# untitled.net
KiCad netlist of a schematic drawn in EAGLE
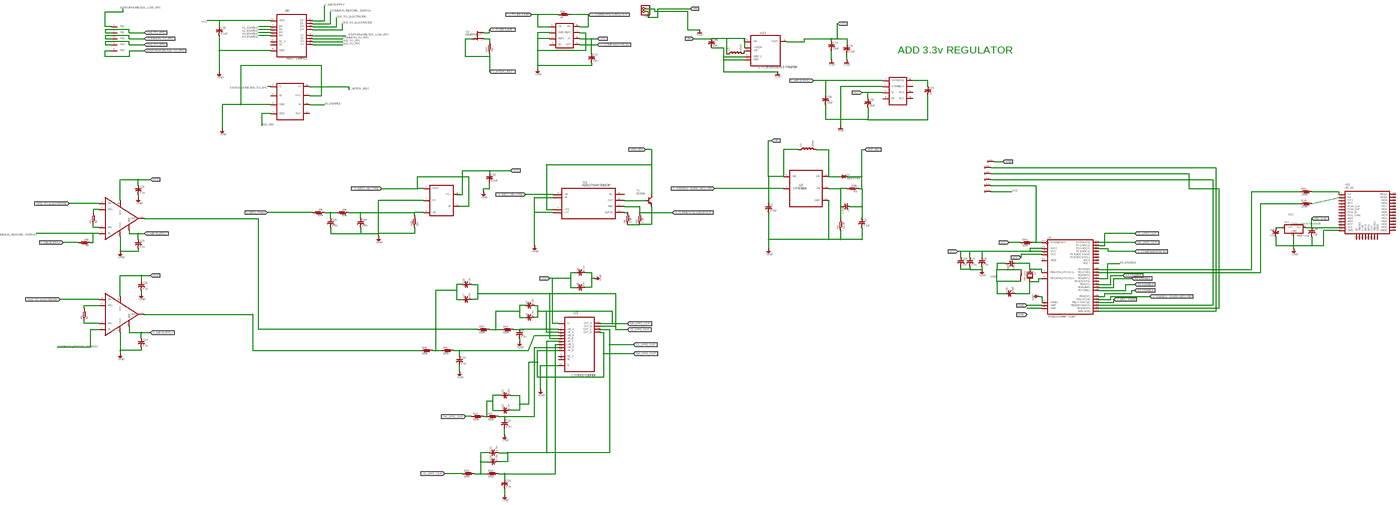
[diagram p0: schematic, sheet 1, overview]
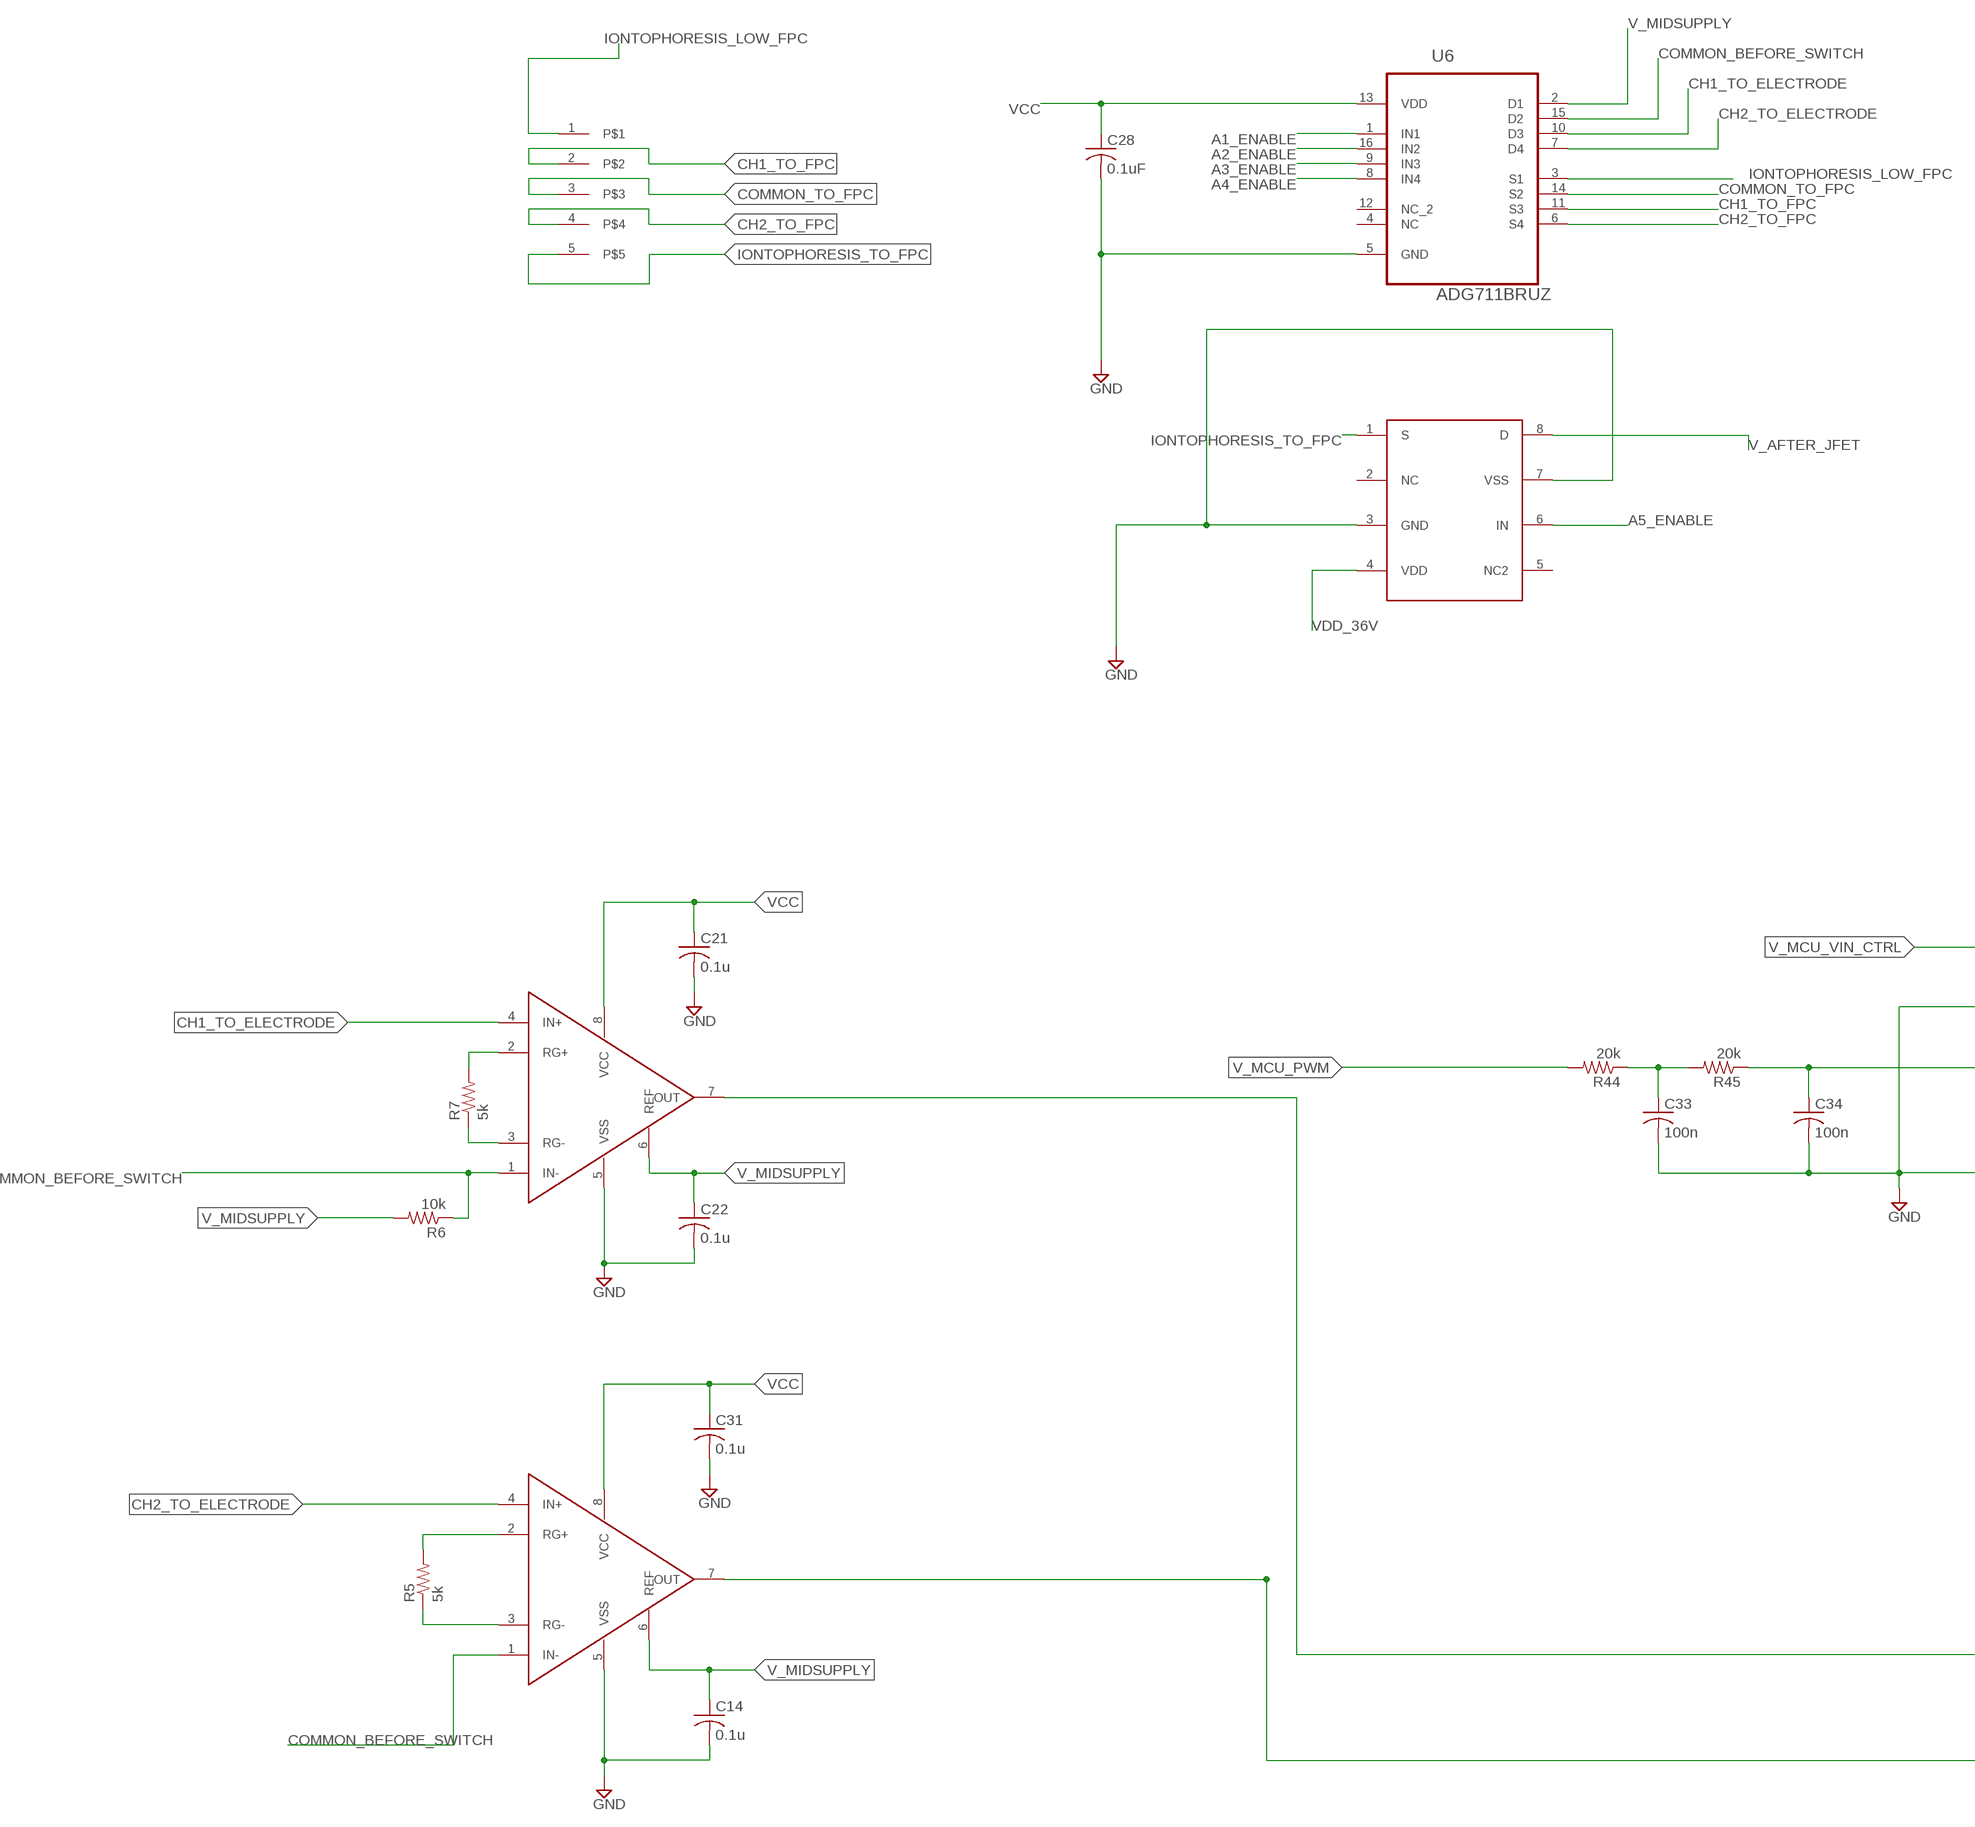
[diagram p1: schematic, sheet 1, part 1 of 4]
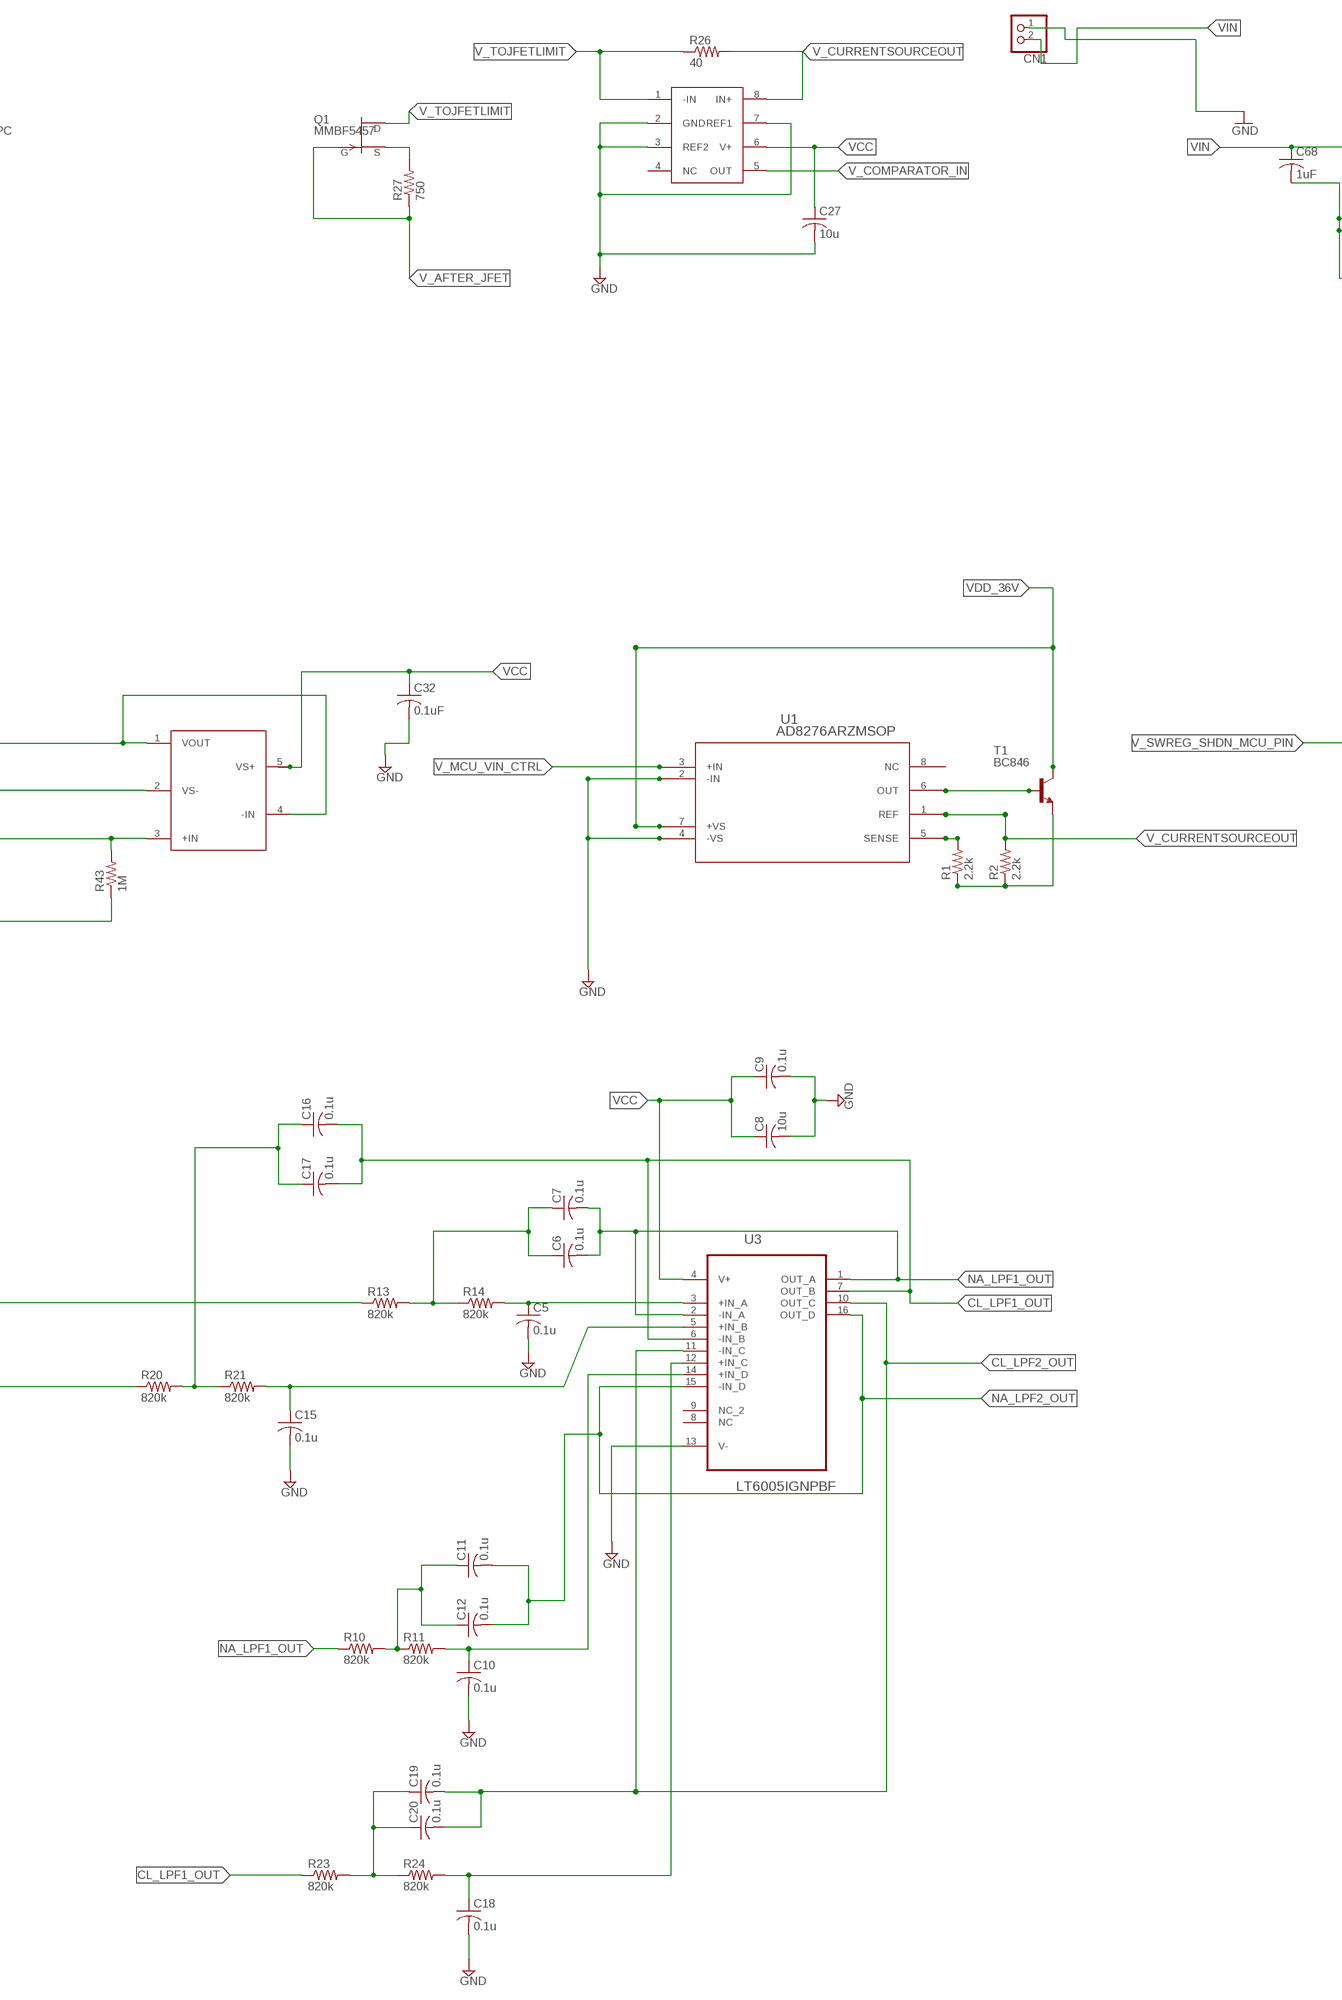
[diagram p2: schematic, sheet 1, part 2 of 4]
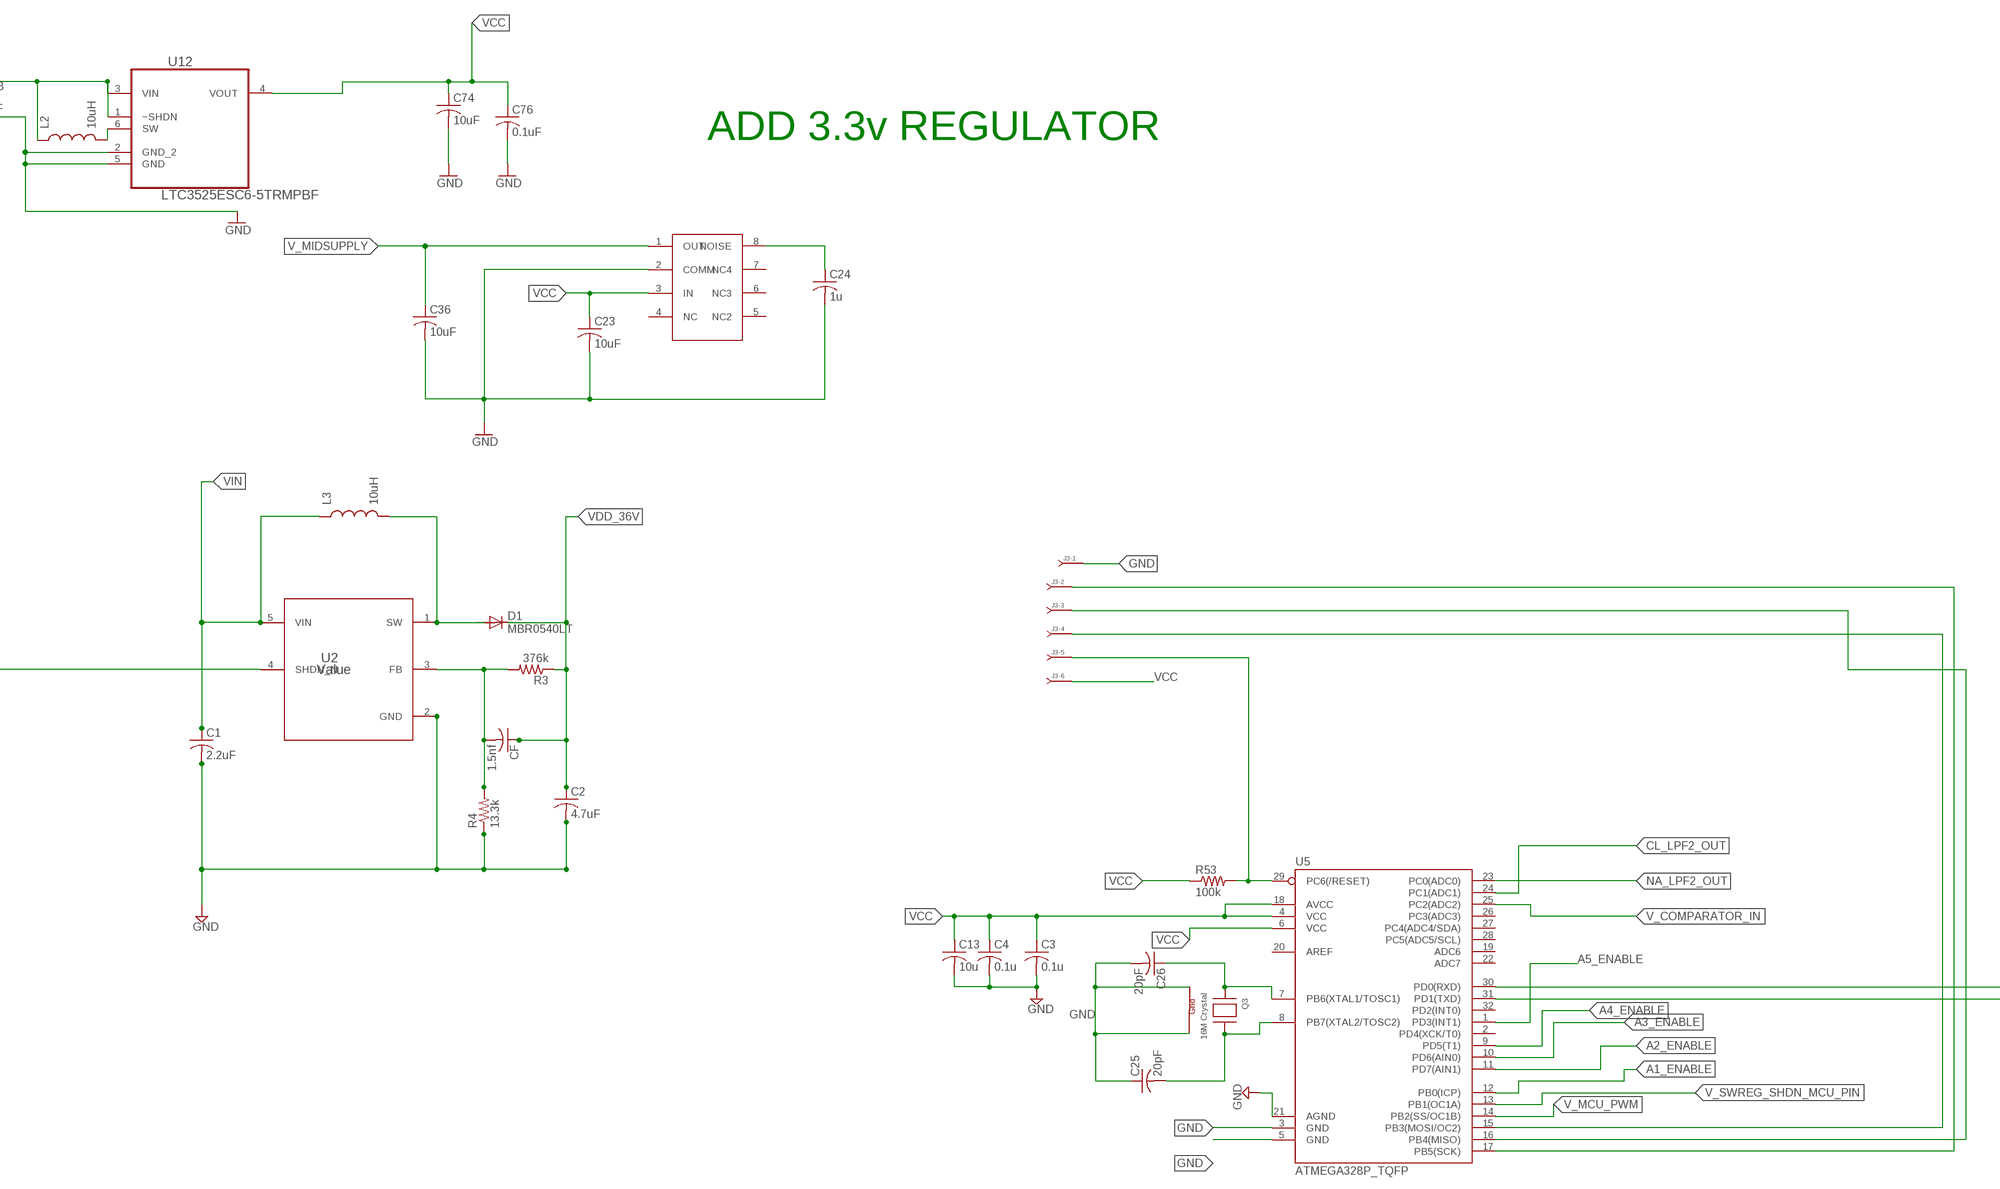
[diagram p3: schematic, sheet 1, part 3 of 4]
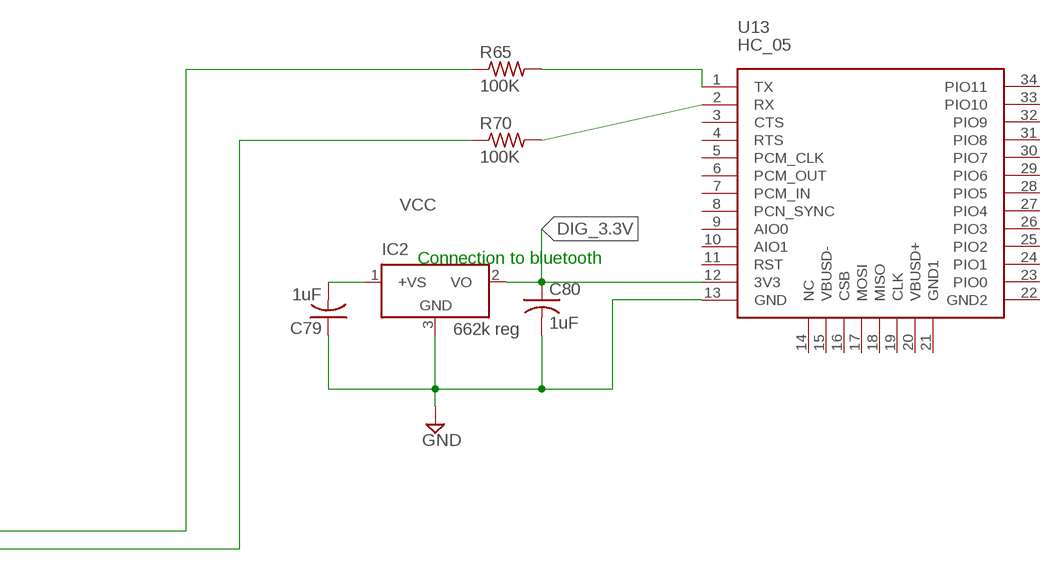
[diagram p4: schematic, sheet 1, part 4 of 4]

(export (version "E")
  (design (tool "Eeschema 10.0.6"))
  (components
    (comp (ref "C1")
      (value "2.2uF")
      (footprint "eagle-import:C0402")
      (libsource (lib "eagle-import") (part "resistor_C-USC0402"))
    )
    (comp (ref "C2")
      (value "4.7uF")
      (footprint "eagle-import:C0603")
      (libsource (lib "eagle-import") (part "resistor_C-USC0603"))
    )
    (comp (ref "C3")
      (value "0.1u")
      (footprint "eagle-import:C0201")
      (libsource (lib "eagle-import") (part "C-USC0201"))
    )
    (comp (ref "C4")
      (value "0.1u")
      (footprint "eagle-import:C0201")
      (libsource (lib "eagle-import") (part "C-USC0201"))
    )
    (comp (ref "C5")
      (value "0.1u")
      (footprint "eagle-import:C0201")
      (libsource (lib "eagle-import") (part "C-USC0201"))
    )
    (comp (ref "C6")
      (value "0.1u")
      (footprint "eagle-import:C0201")
      (libsource (lib "eagle-import") (part "C-USC0201"))
    )
    (comp (ref "C7")
      (value "0.1u")
      (footprint "eagle-import:C0201")
      (libsource (lib "eagle-import") (part "C-USC0201"))
    )
    (comp (ref "C8")
      (value "10u")
      (footprint "eagle-import:C0402")
      (libsource (lib "eagle-import") (part "resistor_C-USC0402"))
    )
    (comp (ref "C9")
      (value "0.1u")
      (footprint "eagle-import:C0201")
      (libsource (lib "eagle-import") (part "C-USC0201"))
    )
    (comp (ref "C10")
      (value "0.1u")
      (footprint "eagle-import:C0201")
      (libsource (lib "eagle-import") (part "C-USC0201"))
    )
    (comp (ref "C11")
      (value "0.1u")
      (footprint "eagle-import:C0201")
      (libsource (lib "eagle-import") (part "C-USC0201"))
    )
    (comp (ref "C12")
      (value "0.1u")
      (footprint "eagle-import:C0201")
      (libsource (lib "eagle-import") (part "C-USC0201"))
    )
    (comp (ref "C13")
      (value "10u")
      (footprint "eagle-import:C0402")
      (libsource (lib "eagle-import") (part "resistor_C-USC0402"))
    )
    (comp (ref "C14")
      (value "0.1u")
      (footprint "eagle-import:C0201")
      (libsource (lib "eagle-import") (part "C-USC0201"))
    )
    (comp (ref "C15")
      (value "0.1u")
      (footprint "eagle-import:C0201")
      (libsource (lib "eagle-import") (part "C-USC0201"))
    )
    (comp (ref "C16")
      (value "0.1u")
      (footprint "eagle-import:C0201")
      (libsource (lib "eagle-import") (part "C-USC0201"))
    )
    (comp (ref "C17")
      (value "0.1u")
      (footprint "eagle-import:C0201")
      (libsource (lib "eagle-import") (part "C-USC0201"))
    )
    (comp (ref "C18")
      (value "0.1u")
      (footprint "eagle-import:C0201")
      (libsource (lib "eagle-import") (part "C-USC0201"))
    )
    (comp (ref "C19")
      (value "0.1u")
      (footprint "eagle-import:C0201")
      (libsource (lib "eagle-import") (part "C-USC0201"))
    )
    (comp (ref "C20")
      (value "0.1u")
      (footprint "eagle-import:C0201")
      (libsource (lib "eagle-import") (part "C-USC0201"))
    )
    (comp (ref "C21")
      (value "0.1u")
      (footprint "eagle-import:C0201")
      (libsource (lib "eagle-import") (part "C-USC0201"))
    )
    (comp (ref "C22")
      (value "0.1u")
      (footprint "eagle-import:C0201")
      (libsource (lib "eagle-import") (part "C-USC0201"))
    )
    (comp (ref "C23")
      (value "10uF")
      (footprint "eagle-import:C0402")
      (libsource (lib "eagle-import") (part "C-USC0402"))
    )
    (comp (ref "C24")
      (value "1u")
      (footprint "eagle-import:C0402")
      (libsource (lib "eagle-import") (part "C-USC0402"))
    )
    (comp (ref "C25")
      (value "20pF")
      (footprint "eagle-import:C0402")
      (libsource (lib "eagle-import") (part "C-USC0402"))
    )
    (comp (ref "C26")
      (value "20pF")
      (footprint "eagle-import:C0402")
      (libsource (lib "eagle-import") (part "C-USC0402"))
    )
    (comp (ref "C27")
      (value "10u")
      (footprint "eagle-import:C0402")
      (libsource (lib "eagle-import") (part "resistor_C-USC0402"))
    )
    (comp (ref "C28")
      (value "0.1uF")
      (footprint "eagle-import:C0201")
      (libsource (lib "eagle-import") (part "C-USC0201"))
    )
    (comp (ref "C31")
      (value "0.1u")
      (footprint "eagle-import:C0201")
      (libsource (lib "eagle-import") (part "C-USC0201"))
    )
    (comp (ref "C32")
      (value "0.1uF")
      (footprint "eagle-import:C0201")
      (libsource (lib "eagle-import") (part "C-USC0201"))
    )
    (comp (ref "C33")
      (value "100n")
      (footprint "eagle-import:C0201")
      (libsource (lib "eagle-import") (part "C-USC0201"))
    )
    (comp (ref "C34")
      (value "100n")
      (footprint "eagle-import:C0201")
      (libsource (lib "eagle-import") (part "C-USC0201"))
    )
    (comp (ref "C36")
      (value "10uF")
      (footprint "eagle-import:C0402")
      (libsource (lib "eagle-import") (part "C-USC0402"))
    )
    (comp (ref "C68")
      (value "1uF")
      (footprint "eagle-import:C0402")
      (fields (field (name "MPN") "MC0402X105M6R3CT"))
      (libsource (lib "eagle-import") (part "C-USC0402"))
    )
    (comp (ref "C74")
      (value "10uF")
      (footprint "eagle-import:C0402")
      (libsource (lib "eagle-import") (part "C-USC0402"))
    )
    (comp (ref "C76")
      (value "0.1uF")
      (footprint "eagle-import:C0402")
      (libsource (lib "eagle-import") (part "C-USC0402"))
    )
    (comp (ref "C79")
      (value "1uF")
      (footprint "eagle-import:C0402")
      (fields (field (name "MPN") "MC0402X105M6R3CT"))
      (libsource (lib "eagle-import") (part "C-USC0402"))
    )
    (comp (ref "C80")
      (value "1uF")
      (footprint "eagle-import:C0402")
      (fields (field (name "MPN") "MC0402X105M6R3CT"))
      (libsource (lib "eagle-import") (part "C-USC0402"))
    )
    (comp (ref "CF")
      (value "1.5nf")
      (footprint "eagle-import:C0402")
      (libsource (lib "eagle-import") (part "resistor_C-USC0402"))
    )
    (comp (ref "CN1")
      (value "JST_2PIN-SMT")
      (footprint "eagle-import:JST-PH-2-SMT")
      (libsource (lib "eagle-import") (part "JST_2PIN-SMT"))
    )
    (comp (ref "D1")
      (value "MBR0540LT")
      (footprint "eagle-import:SOD123")
      (libsource (lib "eagle-import") (part "MBR0540LT"))
    )
    (comp (ref "IC2")
      (value "662k reg")
      (footprint "eagle-import:SOT23")
      (fields (field (name "MF") "NATIONAL SEMICONDUCTOR") (field (name "MPN") "LM5008MM/NOPB"))
      (libsource (lib "eagle-import") (part "LM50"))
    )
    (comp (ref "J3")
      (value "J-06-100-2X03")
      (footprint "eagle-import:HDR-100-2X03")
      (libsource (lib "eagle-import") (part "J-06-100-2X03"))
    )
    (comp (ref "L2")
      (value "10uH")
      (footprint "eagle-import:0805")
      (libsource (lib "eagle-import") (part "INDUCTOR0805"))
    )
    (comp (ref "L3")
      (value "10uH")
      (footprint "eagle-import:0805")
      (libsource (lib "eagle-import") (part "INDUCTOR0805"))
    )
    (comp (ref "Q1")
      (value "MMBF5457")
      (footprint "eagle-import:SOT23")
      (libsource (lib "eagle-import") (part "MMBF5457"))
    )
    (comp (ref "Q3")
      (value "16M Crystal")
      (footprint "eagle-import:NX3225")
      (libsource (lib "eagle-import") (part "XTAL-4-3225"))
    )
    (comp (ref "R1")
      (value "2.2k")
      (footprint "eagle-import:R0201")
      (libsource (lib "eagle-import") (part "R-US_R0201"))
    )
    (comp (ref "R2")
      (value "2.2k")
      (footprint "eagle-import:R0201")
      (libsource (lib "eagle-import") (part "R-US_R0201"))
    )
    (comp (ref "R3")
      (value "376k")
      (footprint "eagle-import:R0402")
      (libsource (lib "eagle-import") (part "R-US_R0402"))
    )
    (comp (ref "R4")
      (value "13.3k")
      (footprint "eagle-import:R0402")
      (libsource (lib "eagle-import") (part "R-US_R0402"))
    )
    (comp (ref "R5")
      (value "5k")
      (footprint "eagle-import:R0201")
      (libsource (lib "eagle-import") (part "R-US_R0201"))
    )
    (comp (ref "R6")
      (value "10k")
      (footprint "eagle-import:R0201")
      (libsource (lib "eagle-import") (part "R-US_R0201"))
    )
    (comp (ref "R7")
      (value "5k")
      (footprint "eagle-import:R0201")
      (libsource (lib "eagle-import") (part "R-US_R0201"))
    )
    (comp (ref "R10")
      (value "820k")
      (footprint "eagle-import:R0201")
      (libsource (lib "eagle-import") (part "R-US_R0201"))
    )
    (comp (ref "R11")
      (value "820k")
      (footprint "eagle-import:R0201")
      (libsource (lib "eagle-import") (part "R-US_R0201"))
    )
    (comp (ref "R13")
      (value "820k")
      (footprint "eagle-import:R0201")
      (libsource (lib "eagle-import") (part "R-US_R0201"))
    )
    (comp (ref "R14")
      (value "820k")
      (footprint "eagle-import:R0201")
      (libsource (lib "eagle-import") (part "R-US_R0201"))
    )
    (comp (ref "R20")
      (value "820k")
      (footprint "eagle-import:R0201")
      (libsource (lib "eagle-import") (part "R-US_R0201"))
    )
    (comp (ref "R21")
      (value "820k")
      (footprint "eagle-import:R0201")
      (libsource (lib "eagle-import") (part "R-US_R0201"))
    )
    (comp (ref "R23")
      (value "820k")
      (footprint "eagle-import:R0201")
      (libsource (lib "eagle-import") (part "R-US_R0201"))
    )
    (comp (ref "R24")
      (value "820k")
      (footprint "eagle-import:R0201")
      (libsource (lib "eagle-import") (part "R-US_R0201"))
    )
    (comp (ref "R26")
      (value "40")
      (footprint "eagle-import:R0201")
      (libsource (lib "eagle-import") (part "R-US_R0201"))
    )
    (comp (ref "R27")
      (value "750")
      (footprint "eagle-import:R0402")
      (libsource (lib "eagle-import") (part "R-US_R0402"))
    )
    (comp (ref "R43")
      (value "1M")
      (footprint "eagle-import:R0201")
      (libsource (lib "eagle-import") (part "R-US_R0201"))
    )
    (comp (ref "R44")
      (value "20k")
      (footprint "eagle-import:R0201")
      (libsource (lib "eagle-import") (part "R-US_R0201"))
    )
    (comp (ref "R45")
      (value "20k")
      (footprint "eagle-import:R0201")
      (libsource (lib "eagle-import") (part "R-US_R0201"))
    )
    (comp (ref "R53")
      (value "100k")
      (footprint "eagle-import:R0201")
      (libsource (lib "eagle-import") (part "R-US_R0201"))
    )
    (comp (ref "R65")
      (value "100K")
      (footprint "eagle-import:R0201")
      (libsource (lib "eagle-import") (part "R-US_R0201"))
    )
    (comp (ref "R70")
      (value "100K")
      (footprint "eagle-import:R0201")
      (libsource (lib "eagle-import") (part "R-US_R0201"))
    )
    (comp (ref "T1")
      (value "BC846")
      (footprint "eagle-import:SOT23")
      (libsource (lib "eagle-import") (part "BC846"))
    )
    (comp (ref "U$1")
      (value "ADG5401")
      (footprint "eagle-import:MSOP08")
      (libsource (lib "eagle-import") (part "ADG5401"))
    )
    (comp (ref "U$5")
      (value "LT1800")
      (footprint "eagle-import:SOT23-5")
      (libsource (lib "eagle-import") (part "LT1800"))
    )
    (comp (ref "U1")
      (value "AD8276ARZMSOP")
      (footprint "eagle-import:MSOP08")
      (libsource (lib "eagle-import") (part "AD8276ARZMSOP"))
    )
    (comp (ref "U2")
      (value "Value")
      (footprint "eagle-import:DBV0005A_N")
      (fields
        (field (name "MANUFACTURER") "Texas Instruments")
        (field (name "PARTNUMBER") "LMR64010XMFE/NOPB")
      )
      (libsource (lib "eagle-import") (part "LMR64010XMFE/NOPB"))
    )
    (comp (ref "U3")
      (value "LT6005IGNPBF")
      (footprint "eagle-import:SOP63P600X175-16N")
      (fields (field (name "MPN") "LT6005IGN#PBF"))
      (libsource (lib "eagle-import") (part "LT6005IGNPBF"))
    )
    (comp (ref "U4")
      (value "INA282")
      (footprint "eagle-import:SO08")
      (libsource (lib "eagle-import") (part "INA282"))
    )
    (comp (ref "U5")
      (value "ATMEGA328P_TQFP")
      (footprint "eagle-import:TQFP32-08")
      (libsource (lib "eagle-import") (part "ATMEGA328P_TQFP"))
    )
    (comp (ref "U6")
      (value "ADG711BRUZ")
      (footprint "eagle-import:SOP65P640X120-16N")
      (libsource (lib "eagle-import") (part "ADG711BRUZ"))
    )
    (comp (ref "U7")
      (value "SOIC8_INAMPMSOP")
      (footprint "eagle-import:MSOP08")
      (libsource (lib "eagle-import") (part "SOIC8_INAMPMSOP"))
    )
    (comp (ref "U8")
      (value "SOIC8_INAMPMSOP")
      (footprint "eagle-import:MSOP08")
      (libsource (lib "eagle-import") (part "SOIC8_INAMPMSOP"))
    )
    (comp (ref "U12")
      (value "LTC3525ESC6-5TRMPBF")
      (footprint "eagle-import:SOT65P210X100-6N")
      (fields (field (name "MPN") "LTC3525ESC6-5#TRMPBF") (field (name "OC_NEWARK") "unknown"))
      (libsource (lib "eagle-import") (part "LTC3525ESC6-5TRMPBF"))
    )
    (comp (ref "U13")
      (value "HC_05")
      (footprint "eagle-import:BLUETOOTH_SMD")
      (libsource (lib "eagle-import") (part "HC_05"))
    )
    (comp (ref "U15")
      (value "TLE2426IDR")
      (footprint "eagle-import:R_8")
      (libsource (lib "eagle-import") (part "TLE2426IDR"))
    )
    (comp (ref "U20")
      (value "FH12-5S-1SH")
      (footprint "eagle-import:FH12-5S-1SH")
      (libsource (lib "eagle-import") (part "FH12-5S-1SH"))
    )
  )
  (nets
    (net (code "1") (name "/A5_ENABLE") (class "Default")
      (node (ref "U$1") (pin "6") (pinfunction "IN_6") (pintype "bidirectional"))
      (node (ref "U5") (pin "1") (pinfunction "PD3(INT1)_1") (pintype "bidirectional"))
    )
    (net (code "2") (name "/COMMON_BEFORE_SWITCH") (class "Default")
      (node (ref "R6") (pin "1") (pinfunction "1_1") (pintype "passive"))
      (node (ref "U6") (pin "15") (pinfunction "D2_15") (pintype "bidirectional"))
      (node (ref "U7") (pin "1") (pinfunction "IN-_1") (pintype "bidirectional"))
      (node (ref "U8") (pin "1") (pinfunction "IN-_1") (pintype "bidirectional"))
    )
    (net (code "3") (name "/IONTOPHORESIS_LOW_FPC") (class "Default")
      (node (ref "U20") (pin "1") (pinfunction "P$1_1") (pintype "bidirectional"))
      (node (ref "U6") (pin "3") (pinfunction "S1_3") (pintype "bidirectional"))
    )
    (net (code "4") (name "A1_ENABLE") (class "Default")
      (node (ref "U5") (pin "12") (pinfunction "PB0(ICP)_12") (pintype "bidirectional"))
      (node (ref "U6") (pin "1") (pinfunction "IN1_1") (pintype "input"))
    )
    (net (code "5") (name "A2_ENABLE") (class "Default")
      (node (ref "U5") (pin "11") (pinfunction "PD7(AIN1)_11") (pintype "bidirectional"))
      (node (ref "U6") (pin "16") (pinfunction "IN2_16") (pintype "input"))
    )
    (net (code "6") (name "A3_ENABLE") (class "Default")
      (node (ref "U5") (pin "10") (pinfunction "PD6(AIN0)_10") (pintype "bidirectional"))
      (node (ref "U6") (pin "9") (pinfunction "IN3_9") (pintype "input"))
    )
    (net (code "7") (name "A4_ENABLE") (class "Default")
      (node (ref "U5") (pin "9") (pinfunction "PD5(T1)_9") (pintype "bidirectional"))
      (node (ref "U6") (pin "8") (pinfunction "IN4_8") (pintype "input"))
    )
    (net (code "8") (name "CH1_TO_ELECTRODE") (class "Default")
      (node (ref "U6") (pin "10") (pinfunction "D3_10") (pintype "bidirectional"))
      (node (ref "U7") (pin "4") (pinfunction "IN+_4") (pintype "bidirectional"))
    )
    (net (code "9") (name "CH1_TO_FPC") (class "Default")
      (node (ref "U20") (pin "2") (pinfunction "P$2_2") (pintype "bidirectional"))
      (node (ref "U6") (pin "11") (pinfunction "S3_11") (pintype "bidirectional"))
    )
    (net (code "10") (name "CH2_TO_ELECTRODE") (class "Default")
      (node (ref "U6") (pin "7") (pinfunction "D4_7") (pintype "bidirectional"))
      (node (ref "U8") (pin "4") (pinfunction "IN+_4") (pintype "bidirectional"))
    )
    (net (code "11") (name "CH2_TO_FPC") (class "Default")
      (node (ref "U20") (pin "4") (pinfunction "P$4_4") (pintype "bidirectional"))
      (node (ref "U6") (pin "6") (pinfunction "S4_6") (pintype "bidirectional"))
    )
    (net (code "12") (name "CL_LPF1_OUT") (class "Default")
      (node (ref "C16") (pin "2") (pinfunction "2_2") (pintype "passive"))
      (node (ref "C17") (pin "2") (pinfunction "2_2") (pintype "passive"))
      (node (ref "R23") (pin "1") (pinfunction "1_1") (pintype "passive"))
      (node (ref "U3") (pin "6") (pinfunction "-IN_B_6") (pintype "input"))
      (node (ref "U3") (pin "7") (pinfunction "OUT_B_7") (pintype "output"))
    )
    (net (code "13") (name "CL_LPF2_OUT") (class "Default")
      (node (ref "C19") (pin "2") (pinfunction "2_2") (pintype "passive"))
      (node (ref "C20") (pin "2") (pinfunction "2_2") (pintype "passive"))
      (node (ref "U3") (pin "10") (pinfunction "OUT_C_10") (pintype "output"))
      (node (ref "U3") (pin "11") (pinfunction "-IN_C_11") (pintype "input"))
      (node (ref "U5") (pin "24") (pinfunction "PC1(ADC1)_24") (pintype "bidirectional"))
    )
    (net (code "14") (name "COMMON_TO_FPC") (class "Default")
      (node (ref "U20") (pin "3") (pinfunction "P$3_3") (pintype "bidirectional"))
      (node (ref "U6") (pin "14") (pinfunction "S2_14") (pintype "bidirectional"))
    )
    (net (code "15") (name "DIG_3.3V") (class "Default")
      (node (ref "C80") (pin "1") (pinfunction "1_1") (pintype "passive"))
      (node (ref "IC2") (pin "2") (pinfunction "VO_2") (pintype "input"))
      (node (ref "U13") (pin "12") (pinfunction "3V3_12") (pintype "bidirectional"))
    )
    (net (code "16") (name "GND") (class "Default")
      (node (ref "C1") (pin "2") (pinfunction "2_2") (pintype "passive"))
      (node (ref "C10") (pin "2") (pinfunction "2_2") (pintype "passive"))
      (node (ref "C13") (pin "2") (pinfunction "2_2") (pintype "passive"))
      (node (ref "C14") (pin "2") (pinfunction "2_2") (pintype "passive"))
      (node (ref "C15") (pin "2") (pinfunction "2_2") (pintype "passive"))
      (node (ref "C18") (pin "2") (pinfunction "2_2") (pintype "passive"))
      (node (ref "C2") (pin "2") (pinfunction "2_2") (pintype "passive"))
      (node (ref "C21") (pin "2") (pinfunction "2_2") (pintype "passive"))
      (node (ref "C22") (pin "2") (pinfunction "2_2") (pintype "passive"))
      (node (ref "C23") (pin "2") (pinfunction "2_2") (pintype "passive"))
      (node (ref "C24") (pin "2") (pinfunction "2_2") (pintype "passive"))
      (node (ref "C25") (pin "1") (pinfunction "1_1") (pintype "passive"))
      (node (ref "C26") (pin "2") (pinfunction "2_2") (pintype "passive"))
      (node (ref "C27") (pin "2") (pinfunction "2_2") (pintype "passive"))
      (node (ref "C28") (pin "2") (pinfunction "2_2") (pintype "passive"))
      (node (ref "C3") (pin "2") (pinfunction "2_2") (pintype "passive"))
      (node (ref "C31") (pin "2") (pinfunction "2_2") (pintype "passive"))
      (node (ref "C32") (pin "2") (pinfunction "2_2") (pintype "passive"))
      (node (ref "C33") (pin "2") (pinfunction "2_2") (pintype "passive"))
      (node (ref "C34") (pin "2") (pinfunction "2_2") (pintype "passive"))
      (node (ref "C36") (pin "2") (pinfunction "2_2") (pintype "passive"))
      (node (ref "C4") (pin "2") (pinfunction "2_2") (pintype "passive"))
      (node (ref "C5") (pin "2") (pinfunction "2_2") (pintype "passive"))
      (node (ref "C68") (pin "2") (pinfunction "2_2") (pintype "passive"))
      (node (ref "C74") (pin "2") (pinfunction "2_2") (pintype "passive"))
      (node (ref "C76") (pin "2") (pinfunction "2_2") (pintype "passive"))
      (node (ref "C79") (pin "1") (pinfunction "1_1") (pintype "passive"))
      (node (ref "C8") (pin "2") (pinfunction "2_2") (pintype "passive"))
      (node (ref "C80") (pin "2") (pinfunction "2_2") (pintype "passive"))
      (node (ref "C9") (pin "2") (pinfunction "2_2") (pintype "passive"))
      (node (ref "CN1") (pin "1") (pinfunction "2_1") (pintype "passive"))
      (node (ref "IC2") (pin "3") (pinfunction "GND_3") (pintype "power_in"))
      (node (ref "J3") (pin "1") (pinfunction "J_1") (pintype "passive"))
      (node (ref "Q3") (pin "2") (pinfunction "G2_2") (pintype "power_in"))
      (node (ref "Q3") (pin "4") (pinfunction "G1_4") (pintype "power_in"))
      (node (ref "R4") (pin "1") (pinfunction "1_1") (pintype "passive"))
      (node (ref "R43") (pin "1") (pinfunction "1_1") (pintype "passive"))
      (node (ref "U$1") (pin "3") (pinfunction "GND_3") (pintype "bidirectional"))
      (node (ref "U$1") (pin "7") (pinfunction "VSS_7") (pintype "bidirectional"))
      (node (ref "U$5") (pin "2") (pinfunction "VS-_2") (pintype "bidirectional"))
      (node (ref "U1") (pin "2") (pinfunction "-IN_2") (pintype "passive"))
      (node (ref "U1") (pin "4") (pinfunction "-VS_4") (pintype "passive"))
      (node (ref "U12") (pin "2") (pinfunction "GND_2_2") (pintype "passive"))
      (node (ref "U12") (pin "5") (pinfunction "GND_5") (pintype "passive"))
      (node (ref "U13") (pin "13") (pinfunction "GND_13") (pintype "bidirectional"))
      (node (ref "U15") (pin "2") (pinfunction "COMM_2") (pintype "bidirectional"))
      (node (ref "U2") (pin "2") (pinfunction "GND_2") (pintype "power_in"))
      (node (ref "U3") (pin "13") (pinfunction "V-_13") (pintype "power_in"))
      (node (ref "U4") (pin "2") (pinfunction "GND_2") (pintype "bidirectional"))
      (node (ref "U4") (pin "3") (pinfunction "REF2_3") (pintype "bidirectional"))
      (node (ref "U4") (pin "7") (pinfunction "REF1_7") (pintype "bidirectional"))
      (node (ref "U5") (pin "21") (pinfunction "AGND_21") (pintype "bidirectional"))
      (node (ref "U5") (pin "3") (pinfunction "GND_3") (pintype "bidirectional"))
      (node (ref "U5") (pin "5") (pinfunction "GND_5") (pintype "bidirectional"))
      (node (ref "U6") (pin "5") (pinfunction "GND_5") (pintype "passive"))
      (node (ref "U7") (pin "5") (pinfunction "VSS_5") (pintype "bidirectional"))
      (node (ref "U8") (pin "5") (pinfunction "VSS_5") (pintype "bidirectional"))
    )
    (net (code "17") (name "IONTOPHORESIS_TO_FPC") (class "Default")
      (node (ref "U$1") (pin "1") (pinfunction "S_1") (pintype "bidirectional"))
      (node (ref "U20") (pin "5") (pinfunction "P$5_5") (pintype "bidirectional"))
    )
    (net (code "18") (name "NA_LPF1_OUT") (class "Default")
      (node (ref "C6") (pin "2") (pinfunction "2_2") (pintype "passive"))
      (node (ref "C7") (pin "2") (pinfunction "2_2") (pintype "passive"))
      (node (ref "R10") (pin "1") (pinfunction "1_1") (pintype "passive"))
      (node (ref "U3") (pin "1") (pinfunction "OUT_A_1") (pintype "output"))
      (node (ref "U3") (pin "2") (pinfunction "-IN_A_2") (pintype "input"))
    )
    (net (code "19") (name "NA_LPF2_OUT") (class "Default")
      (node (ref "C11") (pin "2") (pinfunction "2_2") (pintype "passive"))
      (node (ref "C12") (pin "2") (pinfunction "2_2") (pintype "passive"))
      (node (ref "U3") (pin "15") (pinfunction "-IN_D_15") (pintype "input"))
      (node (ref "U3") (pin "16") (pinfunction "OUT_D_16") (pintype "output"))
      (node (ref "U5") (pin "23") (pinfunction "PC0(ADC0)_23") (pintype "bidirectional"))
    )
    (net (code "20") (name "Net-(C6-Pad1)") (class "Default")
      (node (ref "C6") (pin "1") (pinfunction "1_1") (pintype "passive"))
      (node (ref "C7") (pin "1") (pinfunction "1_1") (pintype "passive"))
      (node (ref "R13") (pin "2") (pinfunction "2_2") (pintype "passive"))
      (node (ref "R14") (pin "1") (pinfunction "1_1") (pintype "passive"))
    )
    (net (code "21") (name "Net-(C11-Pad1)") (class "Default")
      (node (ref "C11") (pin "1") (pinfunction "1_1") (pintype "passive"))
      (node (ref "C12") (pin "1") (pinfunction "1_1") (pintype "passive"))
      (node (ref "R10") (pin "2") (pinfunction "2_2") (pintype "passive"))
      (node (ref "R11") (pin "1") (pinfunction "1_1") (pintype "passive"))
    )
    (net (code "22") (name "Net-(C16-Pad1)") (class "Default")
      (node (ref "C16") (pin "1") (pinfunction "1_1") (pintype "passive"))
      (node (ref "C17") (pin "1") (pinfunction "1_1") (pintype "passive"))
      (node (ref "R20") (pin "2") (pinfunction "2_2") (pintype "passive"))
      (node (ref "R21") (pin "1") (pinfunction "1_1") (pintype "passive"))
    )
    (net (code "23") (name "Net-(C19-Pad1)") (class "Default")
      (node (ref "C19") (pin "1") (pinfunction "1_1") (pintype "passive"))
      (node (ref "C20") (pin "1") (pinfunction "1_1") (pintype "passive"))
      (node (ref "R23") (pin "2") (pinfunction "2_2") (pintype "passive"))
      (node (ref "R24") (pin "1") (pinfunction "1_1") (pintype "passive"))
    )
    (net (code "24") (name "Net-(C33-Pad1)") (class "Default")
      (node (ref "C33") (pin "1") (pinfunction "1_1") (pintype "passive"))
      (node (ref "R44") (pin "1") (pinfunction "1_1") (pintype "passive"))
      (node (ref "R45") (pin "2") (pinfunction "2_2") (pintype "passive"))
    )
    (net (code "25") (name "Net-(J3B-J)") (class "Default")
      (node (ref "J3") (pin "2") (pinfunction "J_2") (pintype "passive"))
      (node (ref "U5") (pin "17") (pinfunction "PB5(SCK)_17") (pintype "bidirectional"))
    )
    (net (code "26") (name "Net-(J3C-J)") (class "Default")
      (node (ref "J3") (pin "3") (pinfunction "J_3") (pintype "passive"))
      (node (ref "U5") (pin "16") (pinfunction "PB4(MISO)_16") (pintype "bidirectional"))
    )
    (net (code "27") (name "Net-(J3D-J)") (class "Default")
      (node (ref "J3") (pin "4") (pinfunction "J_4") (pintype "passive"))
      (node (ref "U5") (pin "15") (pinfunction "PB3(MOSI/OC2)_15") (pintype "bidirectional"))
    )
    (net (code "28") (name "Net-(J3E-J)") (class "Default")
      (node (ref "J3") (pin "5") (pinfunction "J_5") (pintype "passive"))
      (node (ref "R53") (pin "2") (pinfunction "2_2") (pintype "passive"))
      (node (ref "U5") (pin "29") (pinfunction "PC6(/RESET)_29") (pintype "bidirectional"))
    )
    (net (code "29") (name "Net-(Q1-S)") (class "Default")
      (node (ref "Q1") (pin "2") (pinfunction "S_2") (pintype "passive"))
      (node (ref "R27") (pin "2") (pinfunction "2_2") (pintype "passive"))
    )
    (net (code "30") (name "Net-(Q3-X1)") (class "Default")
      (node (ref "C26") (pin "1") (pinfunction "1_1") (pintype "passive"))
      (node (ref "Q3") (pin "1") (pinfunction "X1_1") (pintype "bidirectional"))
      (node (ref "U5") (pin "7") (pinfunction "PB6(XTAL1/TOSC1)_7") (pintype "bidirectional"))
    )
    (net (code "31") (name "Net-(Q3-X2)") (class "Default")
      (node (ref "C25") (pin "2") (pinfunction "2_2") (pintype "passive"))
      (node (ref "Q3") (pin "3") (pinfunction "X2_3") (pintype "bidirectional"))
      (node (ref "U5") (pin "8") (pinfunction "PB7(XTAL2/TOSC2)_8") (pintype "bidirectional"))
    )
    (net (code "32") (name "Net-(T1-B)") (class "Default")
      (node (ref "T1") (pin "1") (pinfunction "B_1") (pintype "passive"))
      (node (ref "U1") (pin "6") (pinfunction "OUT_6") (pintype "passive"))
    )
    (net (code "33") (name "Net-(T1-E)") (class "Default")
      (node (ref "R1") (pin "1") (pinfunction "1_1") (pintype "passive"))
      (node (ref "R2") (pin "1") (pinfunction "1_1") (pintype "passive"))
      (node (ref "T1") (pin "2") (pinfunction "E_2") (pintype "passive"))
    )
    (net (code "34") (name "Net-(U$5-+IN)") (class "Default")
      (node (ref "C34") (pin "1") (pinfunction "1_1") (pintype "passive"))
      (node (ref "R43") (pin "2") (pinfunction "2_2") (pintype "passive"))
      (node (ref "R45") (pin "1") (pinfunction "1_1") (pintype "passive"))
      (node (ref "U$5") (pin "3") (pinfunction "+IN_3") (pintype "bidirectional"))
    )
    (net (code "35") (name "Net-(U1-SENSE)") (class "Default")
      (node (ref "R1") (pin "2") (pinfunction "2_2") (pintype "passive"))
      (node (ref "U1") (pin "5") (pinfunction "SENSE_5") (pintype "passive"))
    )
    (net (code "36") (name "Net-(U2-FB)") (class "Default")
      (node (ref "CF") (pin "2") (pinfunction "2_2") (pintype "passive"))
      (node (ref "R3") (pin "2") (pinfunction "2_2") (pintype "passive"))
      (node (ref "R4") (pin "2") (pinfunction "2_2") (pintype "passive"))
      (node (ref "U2") (pin "3") (pinfunction "FB_3") (pintype "input"))
    )
    (net (code "37") (name "Net-(U2-SW)") (class "Default")
      (node (ref "D1") (pin "A") (pinfunction "A_A") (pintype "passive"))
      (node (ref "L3") (pin "2") (pinfunction "2_2") (pintype "passive"))
      (node (ref "U2") (pin "1") (pinfunction "SW_1") (pintype "power_in"))
    )
    (net (code "38") (name "Net-(U3-+IN_A)") (class "Default")
      (node (ref "C5") (pin "1") (pinfunction "1_1") (pintype "passive"))
      (node (ref "R14") (pin "2") (pinfunction "2_2") (pintype "passive"))
      (node (ref "U3") (pin "3") (pinfunction "+IN_A_3") (pintype "input"))
    )
    (net (code "39") (name "Net-(U3-+IN_B)") (class "Default")
      (node (ref "C15") (pin "1") (pinfunction "1_1") (pintype "passive"))
      (node (ref "R21") (pin "2") (pinfunction "2_2") (pintype "passive"))
      (node (ref "U3") (pin "5") (pinfunction "+IN_B_5") (pintype "input"))
    )
    (net (code "40") (name "Net-(U3-+IN_C)") (class "Default")
      (node (ref "C18") (pin "1") (pinfunction "1_1") (pintype "passive"))
      (node (ref "R24") (pin "2") (pinfunction "2_2") (pintype "passive"))
      (node (ref "U3") (pin "12") (pinfunction "+IN_C_12") (pintype "input"))
    )
    (net (code "41") (name "Net-(U3-+IN_D)") (class "Default")
      (node (ref "C10") (pin "1") (pinfunction "1_1") (pintype "passive"))
      (node (ref "R11") (pin "2") (pinfunction "2_2") (pintype "passive"))
      (node (ref "U3") (pin "14") (pinfunction "+IN_D_14") (pintype "input"))
    )
    (net (code "42") (name "Net-(U5-PD0(RXD))") (class "Default")
      (node (ref "R65") (pin "1") (pinfunction "1_1") (pintype "passive"))
      (node (ref "U5") (pin "30") (pinfunction "PD0(RXD)_30") (pintype "bidirectional"))
    )
    (net (code "43") (name "Net-(U5-PD1(TXD))") (class "Default")
      (node (ref "R70") (pin "1") (pinfunction "1_1") (pintype "passive"))
      (node (ref "U5") (pin "31") (pinfunction "PD1(TXD)_31") (pintype "bidirectional"))
    )
    (net (code "44") (name "Net-(U7-OUT)") (class "Default")
      (node (ref "R13") (pin "1") (pinfunction "1_1") (pintype "passive"))
      (node (ref "U7") (pin "7") (pinfunction "OUT_7") (pintype "bidirectional"))
    )
    (net (code "45") (name "Net-(U7-RG+)") (class "Default")
      (node (ref "R7") (pin "2") (pinfunction "2_2") (pintype "passive"))
      (node (ref "U7") (pin "2") (pinfunction "RG+_2") (pintype "bidirectional"))
    )
    (net (code "46") (name "Net-(U7-RG-)") (class "Default")
      (node (ref "R7") (pin "1") (pinfunction "1_1") (pintype "passive"))
      (node (ref "U7") (pin "3") (pinfunction "RG-_3") (pintype "bidirectional"))
    )
    (net (code "47") (name "Net-(U8-OUT)") (class "Default")
      (node (ref "R20") (pin "1") (pinfunction "1_1") (pintype "passive"))
      (node (ref "U8") (pin "7") (pinfunction "OUT_7") (pintype "bidirectional"))
    )
    (net (code "48") (name "Net-(U8-RG+)") (class "Default")
      (node (ref "R5") (pin "2") (pinfunction "2_2") (pintype "passive"))
      (node (ref "U8") (pin "2") (pinfunction "RG+_2") (pintype "bidirectional"))
    )
    (net (code "49") (name "Net-(U8-RG-)") (class "Default")
      (node (ref "R5") (pin "1") (pinfunction "1_1") (pintype "passive"))
      (node (ref "U8") (pin "3") (pinfunction "RG-_3") (pintype "bidirectional"))
    )
    (net (code "50") (name "Net-(U12-SW)") (class "Default")
      (node (ref "L2") (pin "2") (pinfunction "2_2") (pintype "passive"))
      (node (ref "U12") (pin "6") (pinfunction "SW_6") (pintype "input"))
    )
    (net (code "51") (name "Net-(U13-RX)") (class "Default")
      (node (ref "R70") (pin "2") (pinfunction "2_2") (pintype "passive"))
      (node (ref "U13") (pin "2") (pinfunction "RX_2") (pintype "bidirectional"))
    )
    (net (code "52") (name "Net-(U13-TX)") (class "Default")
      (node (ref "R65") (pin "2") (pinfunction "2_2") (pintype "passive"))
      (node (ref "U13") (pin "1") (pinfunction "TX_1") (pintype "bidirectional"))
    )
    (net (code "53") (name "Net-(U15-NOISE)") (class "Default")
      (node (ref "C24") (pin "1") (pinfunction "1_1") (pintype "passive"))
      (node (ref "U15") (pin "8") (pinfunction "NOISE_8") (pintype "bidirectional"))
    )
    (net (code "54") (name "VCC") (class "Default")
      (node (ref "C13") (pin "1") (pinfunction "1_1") (pintype "passive"))
      (node (ref "C21") (pin "1") (pinfunction "1_1") (pintype "passive"))
      (node (ref "C23") (pin "1") (pinfunction "1_1") (pintype "passive"))
      (node (ref "C27") (pin "1") (pinfunction "1_1") (pintype "passive"))
      (node (ref "C28") (pin "1") (pinfunction "1_1") (pintype "passive"))
      (node (ref "C3") (pin "1") (pinfunction "1_1") (pintype "passive"))
      (node (ref "C31") (pin "1") (pinfunction "1_1") (pintype "passive"))
      (node (ref "C32") (pin "1") (pinfunction "1_1") (pintype "passive"))
      (node (ref "C4") (pin "1") (pinfunction "1_1") (pintype "passive"))
      (node (ref "C74") (pin "1") (pinfunction "1_1") (pintype "passive"))
      (node (ref "C76") (pin "1") (pinfunction "1_1") (pintype "passive"))
      (node (ref "C79") (pin "2") (pinfunction "2_2") (pintype "passive"))
      (node (ref "C8") (pin "1") (pinfunction "1_1") (pintype "passive"))
      (node (ref "C9") (pin "1") (pinfunction "1_1") (pintype "passive"))
      (node (ref "IC2") (pin "1") (pinfunction "+VS_1") (pintype "input"))
      (node (ref "J3") (pin "6") (pinfunction "J_6") (pintype "passive"))
      (node (ref "R53") (pin "1") (pinfunction "1_1") (pintype "passive"))
      (node (ref "U$5") (pin "5") (pinfunction "VS+_5") (pintype "bidirectional"))
      (node (ref "U12") (pin "4") (pinfunction "VOUT_4") (pintype "output"))
      (node (ref "U15") (pin "3") (pinfunction "IN_3") (pintype "bidirectional"))
      (node (ref "U3") (pin "4") (pinfunction "V+_4") (pintype "power_in"))
      (node (ref "U4") (pin "6") (pinfunction "V+_6") (pintype "bidirectional"))
      (node (ref "U5") (pin "18") (pinfunction "AVCC_18") (pintype "bidirectional"))
      (node (ref "U5") (pin "4") (pinfunction "VCC_4") (pintype "bidirectional"))
      (node (ref "U5") (pin "6") (pinfunction "VCC_6") (pintype "bidirectional"))
      (node (ref "U6") (pin "13") (pinfunction "VDD_13") (pintype "power_in"))
      (node (ref "U7") (pin "8") (pinfunction "VCC_8") (pintype "bidirectional"))
      (node (ref "U8") (pin "8") (pinfunction "VCC_8") (pintype "bidirectional"))
    )
    (net (code "55") (name "VDD_36V") (class "Default")
      (node (ref "C2") (pin "1") (pinfunction "1_1") (pintype "passive"))
      (node (ref "CF") (pin "1") (pinfunction "1_1") (pintype "passive"))
      (node (ref "D1") (pin "C") (pinfunction "C_C") (pintype "passive"))
      (node (ref "R3") (pin "1") (pinfunction "1_1") (pintype "passive"))
      (node (ref "T1") (pin "3") (pinfunction "C_3") (pintype "passive"))
      (node (ref "U$1") (pin "4") (pinfunction "VDD_4") (pintype "bidirectional"))
      (node (ref "U1") (pin "7") (pinfunction "+VS_7") (pintype "passive"))
    )
    (net (code "56") (name "VIN") (class "Default")
      (node (ref "C1") (pin "1") (pinfunction "1_1") (pintype "passive"))
      (node (ref "C68") (pin "1") (pinfunction "1_1") (pintype "passive"))
      (node (ref "CN1") (pin "2") (pinfunction "1_2") (pintype "passive"))
      (node (ref "L2") (pin "1") (pinfunction "1_1") (pintype "passive"))
      (node (ref "L3") (pin "1") (pinfunction "1_1") (pintype "passive"))
      (node (ref "U12") (pin "1") (pinfunction "~{SHDN}_1") (pintype "input"))
      (node (ref "U12") (pin "3") (pinfunction "VIN_3") (pintype "input"))
      (node (ref "U2") (pin "5") (pinfunction "VIN_5") (pintype "power_in"))
    )
    (net (code "57") (name "V_AFTER_JFET") (class "Default")
      (node (ref "Q1") (pin "3") (pinfunction "G_3") (pintype "passive"))
      (node (ref "R27") (pin "1") (pinfunction "1_1") (pintype "passive"))
      (node (ref "U$1") (pin "8") (pinfunction "D_8") (pintype "bidirectional"))
    )
    (net (code "58") (name "V_COMPARATOR_IN") (class "Default")
      (node (ref "U4") (pin "5") (pinfunction "OUT_5") (pintype "bidirectional"))
      (node (ref "U5") (pin "25") (pinfunction "PC2(ADC2)_25") (pintype "bidirectional"))
    )
    (net (code "59") (name "V_CURRENTSOURCEOUT") (class "Default")
      (node (ref "R2") (pin "2") (pinfunction "2_2") (pintype "passive"))
      (node (ref "R26") (pin "2") (pinfunction "2_2") (pintype "passive"))
      (node (ref "U1") (pin "1") (pinfunction "REF_1") (pintype "passive"))
      (node (ref "U4") (pin "8") (pinfunction "IN+_8") (pintype "bidirectional"))
    )
    (net (code "60") (name "V_MCU_PWM") (class "Default")
      (node (ref "R44") (pin "2") (pinfunction "2_2") (pintype "passive"))
      (node (ref "U5") (pin "14") (pinfunction "PB2(SS/OC1B)_14") (pintype "bidirectional"))
    )
    (net (code "61") (name "V_MCU_VIN_CTRL") (class "Default")
      (node (ref "U$5") (pin "1") (pinfunction "VOUT_1") (pintype "bidirectional"))
      (node (ref "U$5") (pin "4") (pinfunction "-IN_4") (pintype "bidirectional"))
      (node (ref "U1") (pin "3") (pinfunction "+IN_3") (pintype "passive"))
    )
    (net (code "62") (name "V_MIDSUPPLY") (class "Default")
      (node (ref "C14") (pin "1") (pinfunction "1_1") (pintype "passive"))
      (node (ref "C22") (pin "1") (pinfunction "1_1") (pintype "passive"))
      (node (ref "C36") (pin "1") (pinfunction "1_1") (pintype "passive"))
      (node (ref "R6") (pin "2") (pinfunction "2_2") (pintype "passive"))
      (node (ref "U15") (pin "1") (pinfunction "OUT_1") (pintype "bidirectional"))
      (node (ref "U6") (pin "2") (pinfunction "D1_2") (pintype "bidirectional"))
      (node (ref "U7") (pin "6") (pinfunction "REF_6") (pintype "bidirectional"))
      (node (ref "U8") (pin "6") (pinfunction "REF_6") (pintype "bidirectional"))
    )
    (net (code "63") (name "V_SWREG_SHDN_MCU_PIN") (class "Default")
      (node (ref "U2") (pin "4") (pinfunction "SHDN_N_4") (pintype "input"))
      (node (ref "U5") (pin "13") (pinfunction "PB1(OC1A)_13") (pintype "bidirectional"))
    )
    (net (code "64") (name "V_TOJFETLIMIT") (class "Default")
      (node (ref "Q1") (pin "1") (pinfunction "D_1") (pintype "passive"))
      (node (ref "R26") (pin "1") (pinfunction "1_1") (pintype "passive"))
      (node (ref "U4") (pin "1") (pinfunction "-IN_1") (pintype "bidirectional"))
    )
    (net (code "65") (name "unconnected-(U$1-NC-Pad2)") (class "Default")
      (node (ref "U$1") (pin "2") (pinfunction "NC_2") (pintype "bidirectional"))
    )
    (net (code "66") (name "unconnected-(U$1-NC2-Pad5)") (class "Default")
      (node (ref "U$1") (pin "5") (pinfunction "NC2_5") (pintype "bidirectional"))
    )
    (net (code "67") (name "unconnected-(U1-NC-Pad8)") (class "Default")
      (node (ref "U1") (pin "8") (pinfunction "NC_8") (pintype "passive"))
    )
    (net (code "68") (name "unconnected-(U3-NC-Pad8)") (class "Default")
      (node (ref "U3") (pin "8") (pinfunction "NC_8") (pintype "no_connect"))
    )
    (net (code "69") (name "unconnected-(U3-NC_2-Pad9)") (class "Default")
      (node (ref "U3") (pin "9") (pinfunction "NC_2_9") (pintype "no_connect"))
    )
    (net (code "70") (name "unconnected-(U4-NC-Pad4)") (class "Default")
      (node (ref "U4") (pin "4") (pinfunction "NC_4") (pintype "bidirectional"))
    )
    (net (code "71") (name "unconnected-(U5-ADC6-Pad19)") (class "Default")
      (node (ref "U5") (pin "19") (pinfunction "ADC6_19") (pintype "bidirectional"))
    )
    (net (code "72") (name "unconnected-(U5-ADC7-Pad22)") (class "Default")
      (node (ref "U5") (pin "22") (pinfunction "ADC7_22") (pintype "bidirectional"))
    )
    (net (code "73") (name "unconnected-(U5-AREF-Pad20)") (class "Default")
      (node (ref "U5") (pin "20") (pinfunction "AREF_20") (pintype "bidirectional"))
    )
    (net (code "74") (name "unconnected-(U5-PC3(ADC3)-Pad26)") (class "Default")
      (node (ref "U5") (pin "26") (pinfunction "PC3(ADC3)_26") (pintype "bidirectional"))
    )
    (net (code "75") (name "unconnected-(U5-PC4(ADC4{slash}SDA)-Pad27)") (class "Default")
      (node (ref "U5") (pin "27") (pinfunction "PC4(ADC4/SDA)_27") (pintype "bidirectional"))
    )
    (net (code "76") (name "unconnected-(U5-PC5(ADC5{slash}SCL)-Pad28)") (class "Default")
      (node (ref "U5") (pin "28") (pinfunction "PC5(ADC5/SCL)_28") (pintype "bidirectional"))
    )
    (net (code "77") (name "unconnected-(U5-PD2(INT0)-Pad32)") (class "Default")
      (node (ref "U5") (pin "32") (pinfunction "PD2(INT0)_32") (pintype "bidirectional"))
    )
    (net (code "78") (name "unconnected-(U5-PD4(XCK{slash}T0)-Pad2)") (class "Default")
      (node (ref "U5") (pin "2") (pinfunction "PD4(XCK/T0)_2") (pintype "bidirectional"))
    )
    (net (code "79") (name "unconnected-(U6-NC-Pad4)") (class "Default")
      (node (ref "U6") (pin "4") (pinfunction "NC_4") (pintype "no_connect"))
    )
    (net (code "80") (name "unconnected-(U6-NC_2-Pad12)") (class "Default")
      (node (ref "U6") (pin "12") (pinfunction "NC_2_12") (pintype "no_connect"))
    )
    (net (code "81") (name "unconnected-(U13-AIO0-Pad9)") (class "Default")
      (node (ref "U13") (pin "9") (pinfunction "AIO0_9") (pintype "bidirectional"))
    )
    (net (code "82") (name "unconnected-(U13-AIO1-Pad10)") (class "Default")
      (node (ref "U13") (pin "10") (pinfunction "AIO1_10") (pintype "bidirectional"))
    )
    (net (code "83") (name "unconnected-(U13-CLK-Pad19)") (class "Default")
      (node (ref "U13") (pin "19") (pinfunction "CLK_19") (pintype "bidirectional"))
    )
    (net (code "84") (name "unconnected-(U13-CSB-Pad16)") (class "Default")
      (node (ref "U13") (pin "16") (pinfunction "CSB_16") (pintype "bidirectional"))
    )
    (net (code "85") (name "unconnected-(U13-CTS-Pad3)") (class "Default")
      (node (ref "U13") (pin "3") (pinfunction "CTS_3") (pintype "bidirectional"))
    )
    (net (code "86") (name "unconnected-(U13-GND1-Pad21)") (class "Default")
      (node (ref "U13") (pin "21") (pinfunction "GND1_21") (pintype "bidirectional"))
    )
    (net (code "87") (name "unconnected-(U13-GND2-Pad22)") (class "Default")
      (node (ref "U13") (pin "22") (pinfunction "GND2_22") (pintype "bidirectional"))
    )
    (net (code "88") (name "unconnected-(U13-MISO-Pad18)") (class "Default")
      (node (ref "U13") (pin "18") (pinfunction "MISO_18") (pintype "bidirectional"))
    )
    (net (code "89") (name "unconnected-(U13-MOSI-Pad17)") (class "Default")
      (node (ref "U13") (pin "17") (pinfunction "MOSI_17") (pintype "bidirectional"))
    )
    (net (code "90") (name "unconnected-(U13-NC-Pad14)") (class "Default")
      (node (ref "U13") (pin "14") (pinfunction "NC_14") (pintype "bidirectional"))
    )
    (net (code "91") (name "unconnected-(U13-PCM_CLK-Pad5)") (class "Default")
      (node (ref "U13") (pin "5") (pinfunction "PCM_CLK_5") (pintype "bidirectional"))
    )
    (net (code "92") (name "unconnected-(U13-PCM_IN-Pad7)") (class "Default")
      (node (ref "U13") (pin "7") (pinfunction "PCM_IN_7") (pintype "bidirectional"))
    )
    (net (code "93") (name "unconnected-(U13-PCM_OUT-Pad6)") (class "Default")
      (node (ref "U13") (pin "6") (pinfunction "PCM_OUT_6") (pintype "bidirectional"))
    )
    (net (code "94") (name "unconnected-(U13-PCN_SYNC-Pad8)") (class "Default")
      (node (ref "U13") (pin "8") (pinfunction "PCN_SYNC_8") (pintype "bidirectional"))
    )
    (net (code "95") (name "unconnected-(U13-PIO0-Pad23)") (class "Default")
      (node (ref "U13") (pin "23") (pinfunction "PIO0_23") (pintype "bidirectional"))
    )
    (net (code "96") (name "unconnected-(U13-PIO1-Pad24)") (class "Default")
      (node (ref "U13") (pin "24") (pinfunction "PIO1_24") (pintype "bidirectional"))
    )
    (net (code "97") (name "unconnected-(U13-PIO2-Pad25)") (class "Default")
      (node (ref "U13") (pin "25") (pinfunction "PIO2_25") (pintype "bidirectional"))
    )
    (net (code "98") (name "unconnected-(U13-PIO3-Pad26)") (class "Default")
      (node (ref "U13") (pin "26") (pinfunction "PIO3_26") (pintype "bidirectional"))
    )
    (net (code "99") (name "unconnected-(U13-PIO4-Pad27)") (class "Default")
      (node (ref "U13") (pin "27") (pinfunction "PIO4_27") (pintype "bidirectional"))
    )
    (net (code "100") (name "unconnected-(U13-PIO5-Pad28)") (class "Default")
      (node (ref "U13") (pin "28") (pinfunction "PIO5_28") (pintype "bidirectional"))
    )
    (net (code "101") (name "unconnected-(U13-PIO6-Pad29)") (class "Default")
      (node (ref "U13") (pin "29") (pinfunction "PIO6_29") (pintype "bidirectional"))
    )
    (net (code "102") (name "unconnected-(U13-PIO7-Pad30)") (class "Default")
      (node (ref "U13") (pin "30") (pinfunction "PIO7_30") (pintype "bidirectional"))
    )
    (net (code "103") (name "unconnected-(U13-PIO8-Pad31)") (class "Default")
      (node (ref "U13") (pin "31") (pinfunction "PIO8_31") (pintype "bidirectional"))
    )
    (net (code "104") (name "unconnected-(U13-PIO9-Pad32)") (class "Default")
      (node (ref "U13") (pin "32") (pinfunction "PIO9_32") (pintype "bidirectional"))
    )
    (net (code "105") (name "unconnected-(U13-PIO10-Pad33)") (class "Default")
      (node (ref "U13") (pin "33") (pinfunction "PIO10_33") (pintype "bidirectional"))
    )
    (net (code "106") (name "unconnected-(U13-PIO11-Pad34)") (class "Default")
      (node (ref "U13") (pin "34") (pinfunction "PIO11_34") (pintype "bidirectional"))
    )
    (net (code "107") (name "unconnected-(U13-RST-Pad11)") (class "Default")
      (node (ref "U13") (pin "11") (pinfunction "RST_11") (pintype "bidirectional"))
    )
    (net (code "108") (name "unconnected-(U13-RTS-Pad4)") (class "Default")
      (node (ref "U13") (pin "4") (pinfunction "RTS_4") (pintype "bidirectional"))
    )
    (net (code "109") (name "unconnected-(U13-VBUSD+-Pad20)") (class "Default")
      (node (ref "U13") (pin "20") (pinfunction "VBUSD+_20") (pintype "bidirectional"))
    )
    (net (code "110") (name "unconnected-(U13-VBUSD--Pad15)") (class "Default")
      (node (ref "U13") (pin "15") (pinfunction "VBUSD-_15") (pintype "bidirectional"))
    )
    (net (code "111") (name "unconnected-(U15-NC-Pad4)") (class "Default")
      (node (ref "U15") (pin "4") (pinfunction "NC_4") (pintype "bidirectional"))
    )
    (net (code "112") (name "unconnected-(U15-NC2-Pad5)") (class "Default")
      (node (ref "U15") (pin "5") (pinfunction "NC2_5") (pintype "bidirectional"))
    )
    (net (code "113") (name "unconnected-(U15-NC3-Pad6)") (class "Default")
      (node (ref "U15") (pin "6") (pinfunction "NC3_6") (pintype "bidirectional"))
    )
    (net (code "114") (name "unconnected-(U15-NC4-Pad7)") (class "Default")
      (node (ref "U15") (pin "7") (pinfunction "NC4_7") (pintype "bidirectional"))
    )
  )
)
